# PCB2.net
KiCad netlist of a schematic drawn in EAGLE
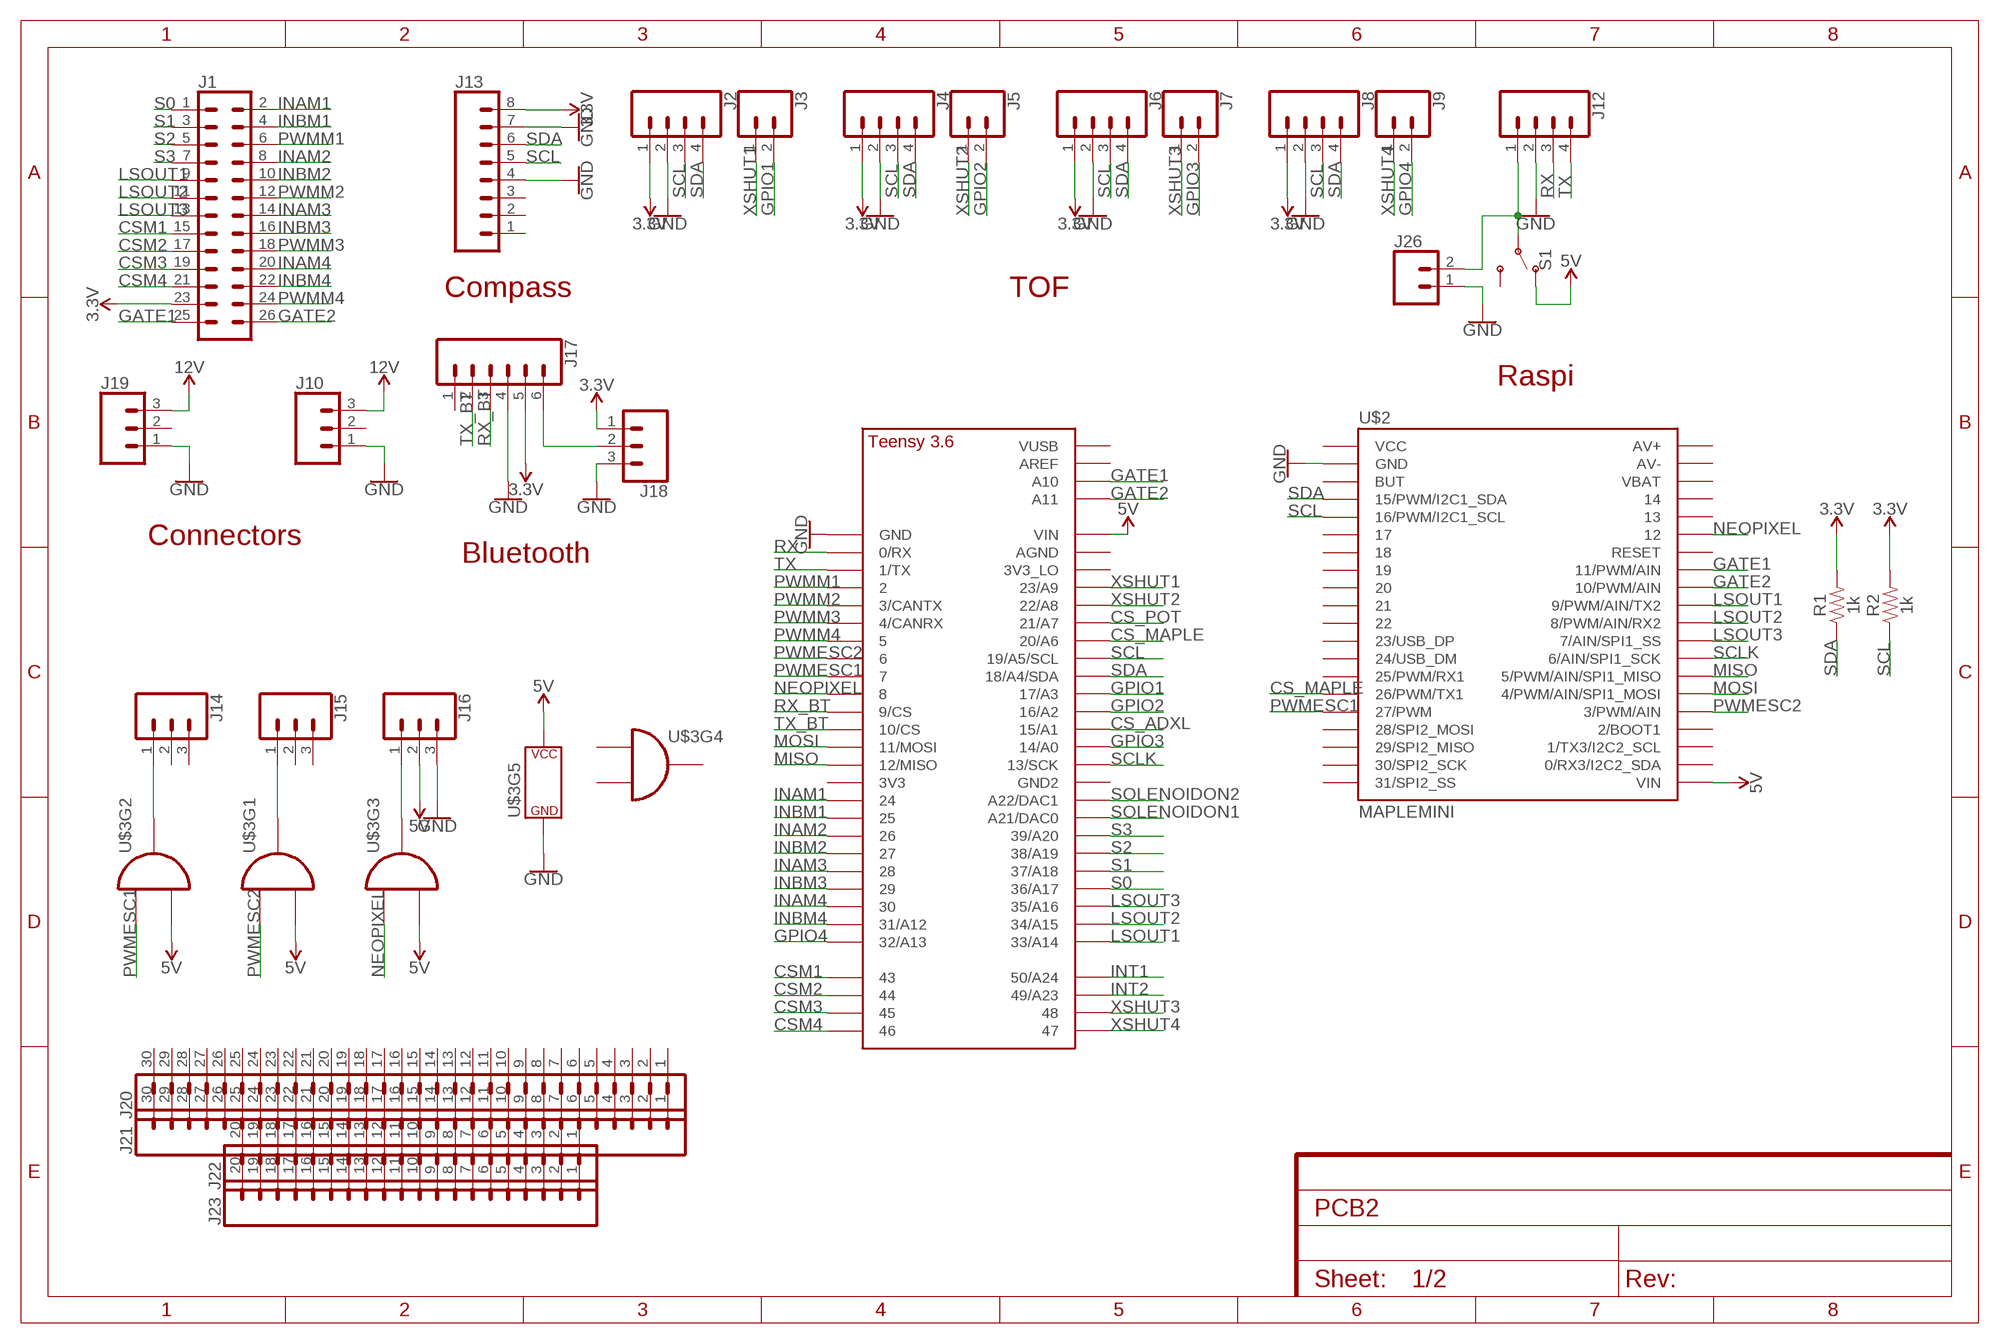
[diagram p0: schematic, sheet 1]
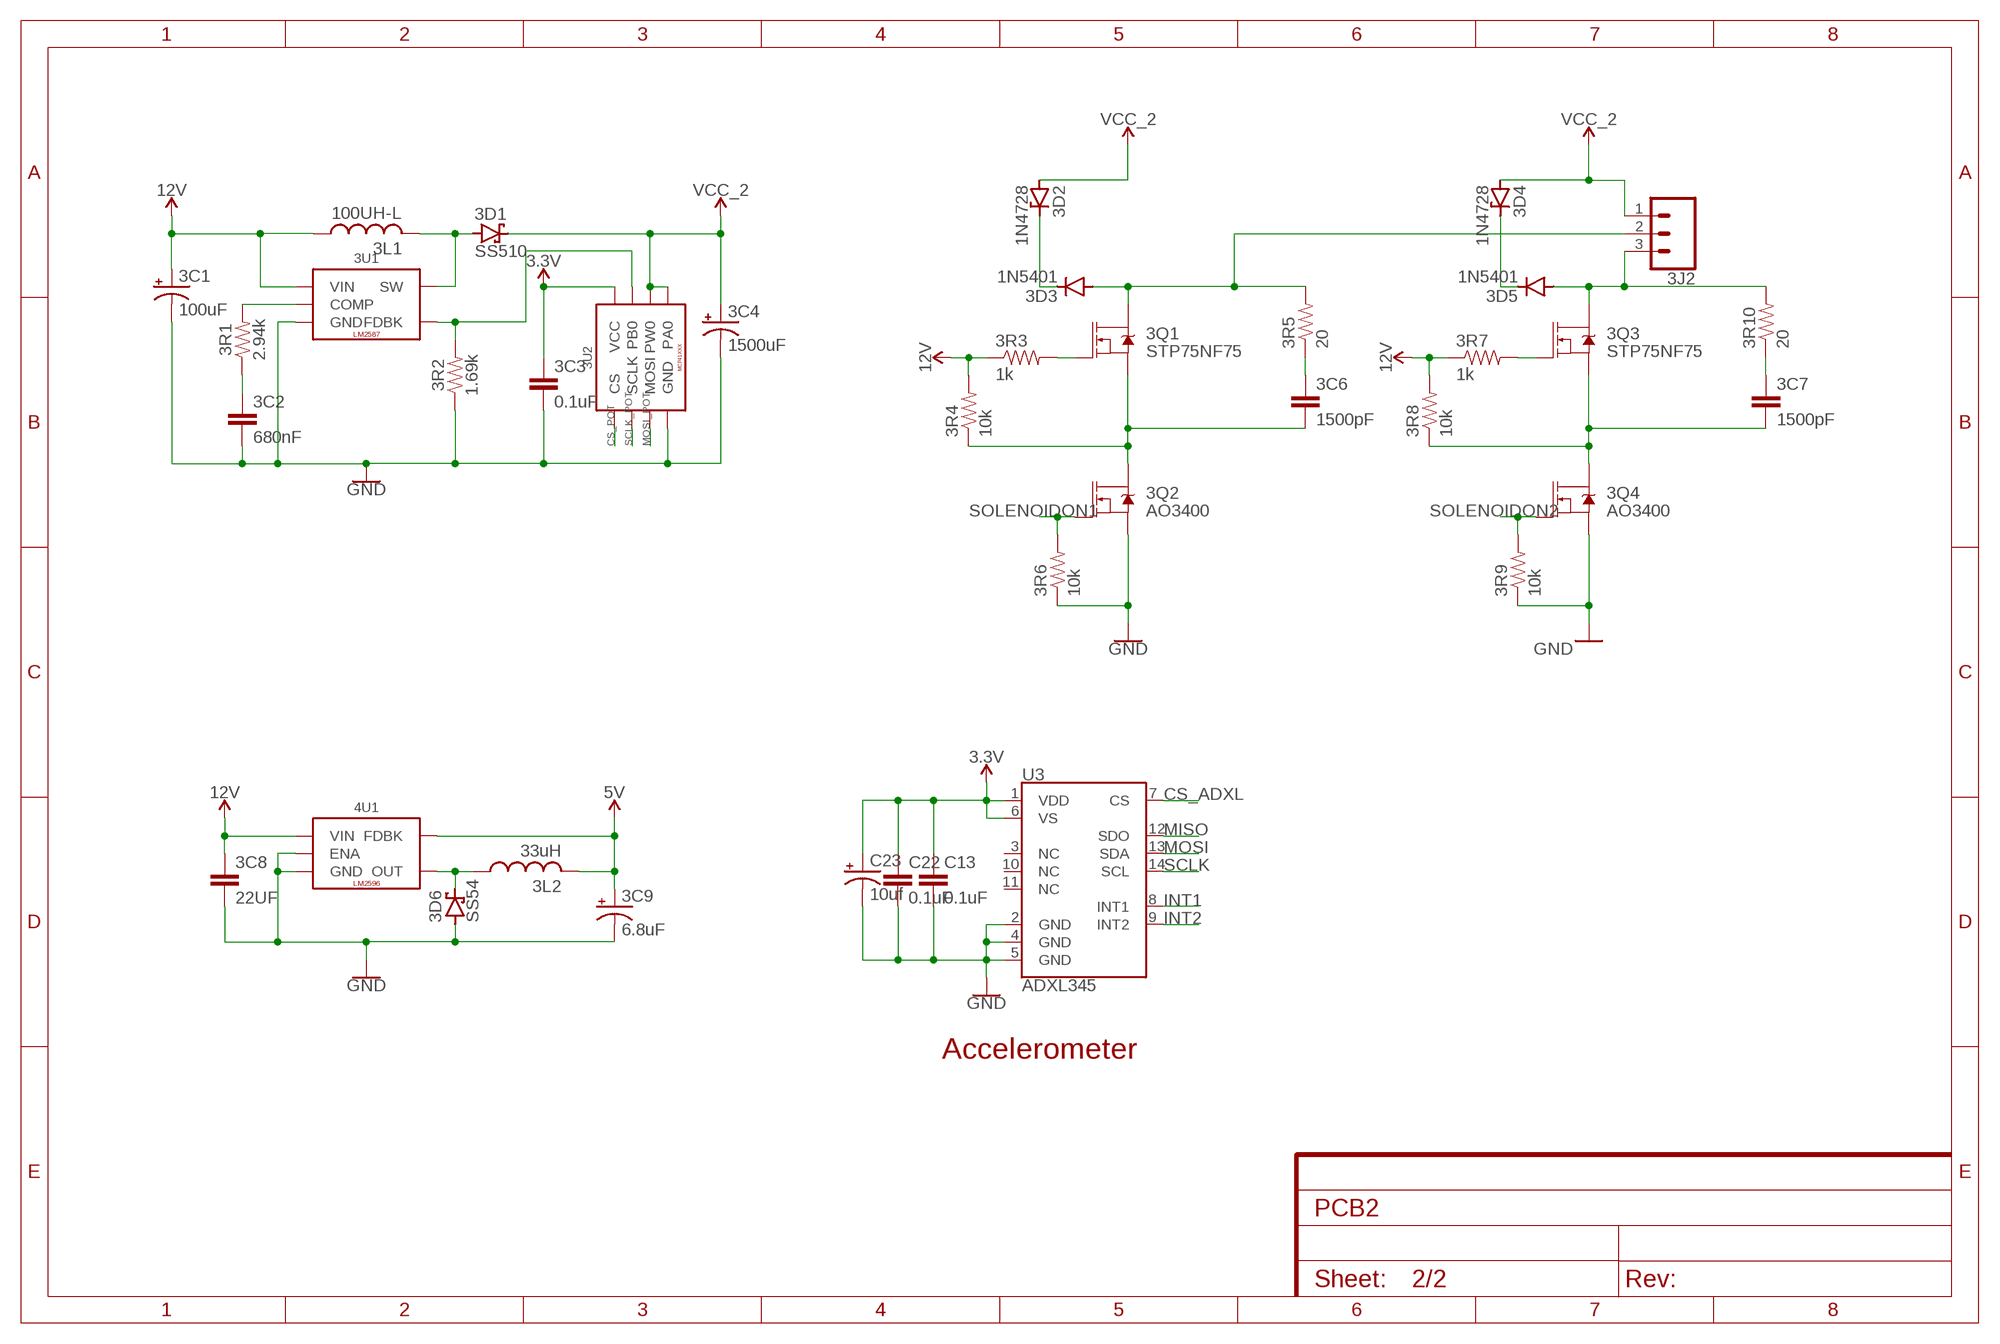
[diagram p1: schematic, sheet 2]

(export (version "E")
  (design (tool "Eeschema 10.0.6"))
  (components
    (comp (ref "J1")
      (value "CONN_13X22X13")
      (footprint "eagle-import:2X13")
      (libsource (lib "eagle-import") (part "CONN_13X22X13"))
    )
    (comp (ref "J2")
      (value "CONN_04LOCK")
      (footprint "eagle-import:1X04_LOCK")
      (libsource (lib "eagle-import") (part "CONN_04LOCK"))
    )
    (comp (ref "J3")
      (value "CONN_02LOCK")
      (footprint "eagle-import:1X02_LOCK")
      (libsource (lib "eagle-import") (part "CONN_02LOCK"))
    )
    (comp (ref "J4")
      (value "CONN_04LOCK")
      (footprint "eagle-import:1X04_LOCK")
      (libsource (lib "eagle-import") (part "CONN_04LOCK"))
    )
    (comp (ref "J5")
      (value "CONN_02LOCK")
      (footprint "eagle-import:1X02_LOCK")
      (libsource (lib "eagle-import") (part "CONN_02LOCK"))
    )
    (comp (ref "J6")
      (value "CONN_04LOCK")
      (footprint "eagle-import:1X04_LOCK")
      (libsource (lib "eagle-import") (part "CONN_04LOCK"))
    )
    (comp (ref "J7")
      (value "CONN_02LOCK")
      (footprint "eagle-import:1X02_LOCK")
      (libsource (lib "eagle-import") (part "CONN_02LOCK"))
    )
    (comp (ref "J8")
      (value "CONN_04LOCK")
      (footprint "eagle-import:1X04_LOCK")
      (libsource (lib "eagle-import") (part "CONN_04LOCK"))
    )
    (comp (ref "J9")
      (value "CONN_02LOCK")
      (footprint "eagle-import:1X02_LOCK")
      (libsource (lib "eagle-import") (part "CONN_02LOCK"))
    )
    (comp (ref "J10")
      (value "CONN_03-SCREW-5MM")
      (footprint "eagle-import:SCREWTERMINAL-5MM-3")
      (libsource (lib "eagle-import") (part "SparkFun-Connectors_513_CONN_03-SCREW-5MM"))
    )
    (comp (ref "J12")
      (value "CONN_04LOCK")
      (footprint "eagle-import:1X04_LOCK")
      (libsource (lib "eagle-import") (part "CONN_04LOCK"))
    )
    (comp (ref "J13")
      (value "CONN_08LOCK")
      (footprint "eagle-import:1X08_LOCK")
      (libsource (lib "eagle-import") (part "CONN_08LOCK"))
    )
    (comp (ref "J14")
      (value "CONN_03LOCK")
      (footprint "eagle-import:1X03_LOCK")
      (libsource (lib "eagle-import") (part "CONN_03LOCK"))
    )
    (comp (ref "J15")
      (value "CONN_03LOCK")
      (footprint "eagle-import:1X03_LOCK")
      (libsource (lib "eagle-import") (part "CONN_03LOCK"))
    )
    (comp (ref "J16")
      (value "CONN_03LOCK")
      (footprint "eagle-import:1X03_LOCK")
      (libsource (lib "eagle-import") (part "CONN_03LOCK"))
    )
    (comp (ref "J17")
      (value "CONN_06LOCK")
      (footprint "eagle-import:1X06_LOCK")
      (libsource (lib "eagle-import") (part "CONN_06LOCK"))
    )
    (comp (ref "J18")
      (value "CONN_03LOCK")
      (footprint "eagle-import:1X03_LOCK")
      (libsource (lib "eagle-import") (part "CONN_03LOCK"))
    )
    (comp (ref "J19")
      (value "CONN_03-SCREW-5MM")
      (footprint "eagle-import:SCREWTERMINAL-5MM-3")
      (libsource (lib "eagle-import") (part "SparkFun-Connectors_513_CONN_03-SCREW-5MM"))
    )
    (comp (ref "J20")
      (value "CONN_30")
      (footprint "eagle-import:1X30")
      (libsource (lib "eagle-import") (part "CONN_30"))
    )
    (comp (ref "J21")
      (value "CONN_30")
      (footprint "eagle-import:1X30")
      (libsource (lib "eagle-import") (part "CONN_30"))
    )
    (comp (ref "J22")
      (value "CONN_20")
      (footprint "eagle-import:1X20")
      (libsource (lib "eagle-import") (part "CONN_20"))
    )
    (comp (ref "J23")
      (value "CONN_20")
      (footprint "eagle-import:1X20")
      (libsource (lib "eagle-import") (part "CONN_20"))
    )
    (comp (ref "J26")
      (value "CONN_02LOCK")
      (footprint "eagle-import:1X02_LOCK")
      (libsource (lib "eagle-import") (part "SparkFun-Connectors_513_CONN_02LOCK"))
    )
    (comp (ref "R1")
      (value "1k")
      (footprint "eagle-import:0603")
      (libsource (lib "eagle-import") (part "1KOHM-0603-1/10W-1%"))
    )
    (comp (ref "R2")
      (value "1k")
      (footprint "eagle-import:0603")
      (libsource (lib "eagle-import") (part "1KOHM-0603-1/10W-1%"))
    )
    (comp (ref "S1")
      (value "SWITCH-SPDT-PTH-11.6X4.0MM-LOCK")
      (footprint "eagle-import:SWITCH_SPDT_PTH_11.6X4.0MM_LOCK")
      (libsource (lib "eagle-import") (part "SWITCH-SPDT-PTH-11.6X4.0MM-LOCK"))
    )
    (comp (ref "U$1")
      (value "TEENSY_3.5/3.6_BASIC")
      (footprint "eagle-import:TEENSY_3.5_3.6_BASIC")
      (libsource (lib "eagle-import") (part "TEENSY_3.5/3.6_BASIC"))
    )
    (comp (ref "U$2")
      (value "MAPLEMINI")
      (footprint "eagle-import:20-DIP")
      (libsource (lib "eagle-import") (part "MAPLEMINI"))
    )
    (comp (ref "U$3")
      (value "74HCT08")
      (footprint "eagle-import:SOIC-14")
      (libsource (lib "eagle-import") (part "74HCT08"))
    )
    (comp (ref "3C1")
      (value "100uF")
      (footprint "eagle-import:PANASONIC_D")
      (libsource (lib "eagle-import") (part "100UF-POLAR-25V-20%(ELEC)"))
    )
    (comp (ref "3C2")
      (value "680nF")
      (footprint "eagle-import:0603")
      (libsource (lib "eagle-import") (part "680PF-0603-50V-10%"))
    )
    (comp (ref "3C3")
      (value "0.1uF")
      (footprint "eagle-import:0603")
      (libsource (lib "eagle-import") (part "0.1UF-0603-25V-5%"))
    )
    (comp (ref "3C4")
      (value "1500uF")
      (footprint "eagle-import:1000UF-CAP")
      (libsource (lib "eagle-import") (part "1000UF-CAP"))
    )
    (comp (ref "3C6")
      (value "1500pF")
      (footprint "eagle-import:0603")
      (libsource (lib "eagle-import") (part "1.5PF-0603-50V-16.667%"))
    )
    (comp (ref "3C7")
      (value "1500pF")
      (footprint "eagle-import:0603")
      (libsource (lib "eagle-import") (part "1.5PF-0603-50V-16.667%"))
    )
    (comp (ref "3C8")
      (value "22UF")
      (footprint "eagle-import:1210")
      (libsource (lib "eagle-import") (part "22UF-1210-16V-20%"))
    )
    (comp (ref "3C9")
      (value "6.8uF")
      (footprint "eagle-import:A_3216-18R")
      (libsource (lib "eagle-import") (part "CPOL-USA/3216-18R"))
    )
    (comp (ref "3D1")
      (value "SS510")
      (footprint "eagle-import:SMB")
      (libsource (lib "eagle-import") (part "SCHOTTKY-DIODESMD"))
    )
    (comp (ref "3D2")
      (value "1N4728")
      (footprint "eagle-import:DO41Z10")
      (libsource (lib "eagle-import") (part "1N4728"))
    )
    (comp (ref "3D3")
      (value "1N5401")
      (footprint "eagle-import:DO201-15")
      (libsource (lib "eagle-import") (part "1N5400"))
    )
    (comp (ref "3D4")
      (value "1N4728")
      (footprint "eagle-import:DO41Z10")
      (libsource (lib "eagle-import") (part "1N4728"))
    )
    (comp (ref "3D5")
      (value "1N5401")
      (footprint "eagle-import:DO201-15")
      (libsource (lib "eagle-import") (part "1N5400"))
    )
    (comp (ref "3D6")
      (value "SS54")
      (footprint "eagle-import:SMB")
      (libsource (lib "eagle-import") (part "SCHOTTKY-DIODESMD"))
    )
    (comp (ref "3J2")
      (value "CONN_03-SCREW-5MM")
      (footprint "eagle-import:SCREWTERMINAL-5MM-3")
      (libsource (lib "eagle-import") (part "CONN_03-SCREW-5MM"))
    )
    (comp (ref "3L1")
      (value "100UH-L")
      (footprint "eagle-import:100UH-L")
      (libsource (lib "eagle-import") (part "100UH-L"))
    )
    (comp (ref "3L2")
      (value "33uH")
      (footprint "eagle-import:127")
      (libsource (lib "eagle-import") (part "CDRH127"))
    )
    (comp (ref "3Q1")
      (value "STP75NF75")
      (footprint "eagle-import:TO220V")
      (libsource (lib "eagle-import") (part "MOSFET-NCH-FQP30N06L"))
    )
    (comp (ref "3Q2")
      (value "AO3400")
      (footprint "eagle-import:SOT23-3")
      (libsource (lib "eagle-import") (part "MOSFET-NCH-AO3404A"))
    )
    (comp (ref "3Q3")
      (value "STP75NF75")
      (footprint "eagle-import:TO220V")
      (libsource (lib "eagle-import") (part "MOSFET-NCH-FQP30N06L"))
    )
    (comp (ref "3Q4")
      (value "AO3400")
      (footprint "eagle-import:SOT23-3")
      (libsource (lib "eagle-import") (part "MOSFET-NCH-AO3404A"))
    )
    (comp (ref "3R1")
      (value "2.94k")
      (footprint "eagle-import:0603")
      (libsource (lib "eagle-import") (part "RESISTOR0603"))
    )
    (comp (ref "3R2")
      (value "1.69k")
      (footprint "eagle-import:0603")
      (libsource (lib "eagle-import") (part "2.0KOHM-0603-1/10W-5%"))
    )
    (comp (ref "3R3")
      (value "1k")
      (footprint "eagle-import:0603")
      (libsource (lib "eagle-import") (part "1KOHM-0603-1/10W-1%"))
    )
    (comp (ref "3R4")
      (value "10k")
      (footprint "eagle-import:0603")
      (libsource (lib "eagle-import") (part "10KOHM-0603-1/10W-1%"))
    )
    (comp (ref "3R5")
      (value "20")
      (footprint "eagle-import:0603")
      (libsource (lib "eagle-import") (part "20OHM-0603-1/10W-1%"))
    )
    (comp (ref "3R6")
      (value "10k")
      (footprint "eagle-import:0603")
      (libsource (lib "eagle-import") (part "10KOHM-0603-1/10W-1%"))
    )
    (comp (ref "3R7")
      (value "1k")
      (footprint "eagle-import:0603")
      (libsource (lib "eagle-import") (part "1KOHM-0603-1/10W-1%"))
    )
    (comp (ref "3R8")
      (value "10k")
      (footprint "eagle-import:0603")
      (libsource (lib "eagle-import") (part "10KOHM-0603-1/10W-1%"))
    )
    (comp (ref "3R9")
      (value "10k")
      (footprint "eagle-import:0603")
      (libsource (lib "eagle-import") (part "10KOHM-0603-1/10W-1%"))
    )
    (comp (ref "3R10")
      (value "20")
      (footprint "eagle-import:0603")
      (libsource (lib "eagle-import") (part "20OHM-0603-1/10W-1%"))
    )
    (comp (ref "3U1")
      (value "LM2587")
      (footprint "eagle-import:TO-263")
      (libsource (lib "eagle-import") (part "LM2587"))
    )
    (comp (ref "3U2")
      (value "MCP41XXX")
      (footprint "eagle-import:SOIC-8")
      (libsource (lib "eagle-import") (part "MCP41XXX"))
    )
    (comp (ref "4U1")
      (value "LM2596")
      (footprint "eagle-import:TO-263")
      (libsource (lib "eagle-import") (part "LM2596"))
    )
    (comp (ref "C13")
      (value "0.1uF")
      (footprint "eagle-import:0603")
      (libsource (lib "eagle-import") (part "0.1UF-0603-100V-10%"))
    )
    (comp (ref "C22")
      (value "0.1uF")
      (footprint "eagle-import:0603")
      (libsource (lib "eagle-import") (part "0.1UF-0603-100V-10%"))
    )
    (comp (ref "C23")
      (value "10uf")
      (footprint "eagle-import:R_2012-12R")
      (libsource (lib "eagle-import") (part "CPOL-USR/2012-12R"))
    )
    (comp (ref "U3")
      (value "ADXL345")
      (footprint "eagle-import:LGA-14")
      (libsource (lib "eagle-import") (part "ADXL345"))
    )
  )
  (nets
    (net (code "1") (name "3.3V") (class "Default")
      (node (ref "3C3") (pin "1") (pinfunction "1_1") (pintype "passive"))
      (node (ref "3U2") (pin "8") (pinfunction "VCC_8") (pintype "power_in"))
      (node (ref "C13") (pin "1") (pinfunction "1_1") (pintype "passive"))
      (node (ref "C22") (pin "1") (pinfunction "1_1") (pintype "passive"))
      (node (ref "C23") (pin "+") (pinfunction "+_+") (pintype "passive"))
      (node (ref "J1") (pin "23") (pinfunction "23_23") (pintype "passive"))
      (node (ref "J13") (pin "8") (pinfunction "8_8") (pintype "passive"))
      (node (ref "J17") (pin "5") (pinfunction "5_5") (pintype "passive"))
      (node (ref "J18") (pin "1") (pinfunction "1_1") (pintype "passive"))
      (node (ref "J2") (pin "1") (pinfunction "1_1") (pintype "passive"))
      (node (ref "J4") (pin "1") (pinfunction "1_1") (pintype "passive"))
      (node (ref "J6") (pin "1") (pinfunction "1_1") (pintype "passive"))
      (node (ref "J8") (pin "1") (pinfunction "1_1") (pintype "passive"))
      (node (ref "R1") (pin "2") (pinfunction "2_2") (pintype "passive"))
      (node (ref "R2") (pin "2") (pinfunction "2_2") (pintype "passive"))
      (node (ref "U3") (pin "1") (pinfunction "VDD_1") (pintype "bidirectional"))
      (node (ref "U3") (pin "6") (pinfunction "VS_6") (pintype "bidirectional"))
    )
    (net (code "2") (name "5V") (class "Default")
      (node (ref "3C9") (pin "+") (pinfunction "+_+") (pintype "passive"))
      (node (ref "3L2") (pin "2") (pinfunction "2_2") (pintype "passive"))
      (node (ref "4U1") (pin "P4") (pinfunction "FDBK_P4") (pintype "output"))
      (node (ref "J16") (pin "2") (pinfunction "2_2") (pintype "passive"))
      (node (ref "S1") (pin "1") (pinfunction "O_1") (pintype "passive"))
      (node (ref "U$1") (pin "VIN") (pinfunction "VIN_VIN") (pintype "bidirectional"))
      (node (ref "U$2") (pin "21") (pinfunction "VIN_21") (pintype "bidirectional"))
      (node (ref "U$3") (pin "P10") (pinfunction "I1_P10") (pintype "input"))
      (node (ref "U$3") (pin "P14") (pinfunction "P$V+_P14") (pintype "bidirectional"))
      (node (ref "U$3") (pin "P2") (pinfunction "I1_P2") (pintype "input"))
      (node (ref "U$3") (pin "P5") (pinfunction "I1_P5") (pintype "input"))
    )
    (net (code "3") (name "12V") (class "Default")
      (node (ref "3C1") (pin "+") (pinfunction "+_+") (pintype "passive"))
      (node (ref "3C8") (pin "1") (pinfunction "1_1") (pintype "passive"))
      (node (ref "3L1") (pin "P1") (pinfunction "1_P1") (pintype "passive"))
      (node (ref "3R3") (pin "1") (pinfunction "1_1") (pintype "passive"))
      (node (ref "3R4") (pin "2") (pinfunction "2_2") (pintype "passive"))
      (node (ref "3R7") (pin "1") (pinfunction "1_1") (pintype "passive"))
      (node (ref "3R8") (pin "2") (pinfunction "2_2") (pintype "passive"))
      (node (ref "3U1") (pin "P5") (pinfunction "VIN_P5") (pintype "power_in"))
      (node (ref "4U1") (pin "P1") (pinfunction "VIN_P1") (pintype "power_in"))
      (node (ref "J10") (pin "3") (pinfunction "3_3") (pintype "passive"))
      (node (ref "J19") (pin "3") (pinfunction "3_3") (pintype "passive"))
    )
    (net (code "4") (name "CSM1") (class "Default")
      (node (ref "J1") (pin "15") (pinfunction "15_15") (pintype "passive"))
      (node (ref "U$1") (pin "43") (pinfunction "43_43") (pintype "bidirectional"))
    )
    (net (code "5") (name "CSM2") (class "Default")
      (node (ref "J1") (pin "17") (pinfunction "17_17") (pintype "passive"))
      (node (ref "U$1") (pin "44") (pinfunction "44_44") (pintype "bidirectional"))
    )
    (net (code "6") (name "CSM3") (class "Default")
      (node (ref "J1") (pin "19") (pinfunction "19_19") (pintype "passive"))
      (node (ref "U$1") (pin "45") (pinfunction "45_45") (pintype "bidirectional"))
    )
    (net (code "7") (name "CSM4") (class "Default")
      (node (ref "J1") (pin "21") (pinfunction "21_21") (pintype "passive"))
      (node (ref "U$1") (pin "46") (pinfunction "46_46") (pintype "bidirectional"))
    )
    (net (code "8") (name "CS_ADXL") (class "Default")
      (node (ref "U$1") (pin "15/A1") (pinfunction "15/A1_15/A1") (pintype "bidirectional"))
      (node (ref "U3") (pin "7") (pinfunction "CS_7") (pintype "bidirectional"))
    )
    (net (code "9") (name "CS_MAPLE") (class "Default")
      (node (ref "U$1") (pin "20/A6") (pinfunction "20/A6_20/A6") (pintype "bidirectional"))
      (node (ref "U$2") (pin "15") (pinfunction "26/PWM/TX1_15") (pintype "bidirectional"))
    )
    (net (code "10") (name "CS_POT") (class "Default")
      (node (ref "3U2") (pin "1") (pinfunction "CS_1") (pintype "input"))
      (node (ref "U$1") (pin "21/A7") (pinfunction "21/A7_21/A7") (pintype "bidirectional"))
    )
    (net (code "11") (name "GATE1") (class "Default")
      (node (ref "J1") (pin "25") (pinfunction "25_25") (pintype "passive"))
      (node (ref "U$1") (pin "A10") (pinfunction "A10_A10") (pintype "bidirectional"))
      (node (ref "U$2") (pin "33") (pinfunction "11/PWM/AIN_33") (pintype "bidirectional"))
    )
    (net (code "12") (name "GATE2") (class "Default")
      (node (ref "J1") (pin "26") (pinfunction "26_26") (pintype "passive"))
      (node (ref "U$1") (pin "A11") (pinfunction "A11_A11") (pintype "bidirectional"))
      (node (ref "U$2") (pin "32") (pinfunction "10/PWM/AIN_32") (pintype "bidirectional"))
    )
    (net (code "13") (name "GND") (class "Default")
      (node (ref "3C1") (pin "-") (pinfunction "-_-") (pintype "passive"))
      (node (ref "3C2") (pin "2") (pinfunction "2_2") (pintype "passive"))
      (node (ref "3C3") (pin "2") (pinfunction "2_2") (pintype "passive"))
      (node (ref "3C4") (pin "-") (pinfunction "-_-") (pintype "passive"))
      (node (ref "3C8") (pin "2") (pinfunction "2_2") (pintype "passive"))
      (node (ref "3C9") (pin "-") (pinfunction "-_-") (pintype "passive"))
      (node (ref "3D6") (pin "A") (pinfunction "A_A") (pintype "passive"))
      (node (ref "3Q2") (pin "2") (pinfunction "S_2") (pintype "bidirectional"))
      (node (ref "3Q4") (pin "2") (pinfunction "S_2") (pintype "bidirectional"))
      (node (ref "3R2") (pin "1") (pinfunction "1_1") (pintype "passive"))
      (node (ref "3R6") (pin "1") (pinfunction "1_1") (pintype "passive"))
      (node (ref "3R9") (pin "1") (pinfunction "1_1") (pintype "passive"))
      (node (ref "3U1") (pin "P3") (pinfunction "GND_P3") (pintype "power_in"))
      (node (ref "3U2") (pin "4") (pinfunction "GND_4") (pintype "power_in"))
      (node (ref "4U1") (pin "P3") (pinfunction "GND_P3") (pintype "power_in"))
      (node (ref "4U1") (pin "P5") (pinfunction "ENA_P5") (pintype "bidirectional"))
      (node (ref "4U1") (pin "TAB") (pinfunction "GND_TAB") (pintype "power_in"))
      (node (ref "C13") (pin "2") (pinfunction "2_2") (pintype "passive"))
      (node (ref "C22") (pin "2") (pinfunction "2_2") (pintype "passive"))
      (node (ref "C23") (pin "-") (pinfunction "-_-") (pintype "passive"))
      (node (ref "J10") (pin "1") (pinfunction "1_1") (pintype "passive"))
      (node (ref "J12") (pin "2") (pinfunction "2_2") (pintype "passive"))
      (node (ref "J13") (pin "4") (pinfunction "4_4") (pintype "passive"))
      (node (ref "J13") (pin "7") (pinfunction "7_7") (pintype "passive"))
      (node (ref "J16") (pin "3") (pinfunction "3_3") (pintype "passive"))
      (node (ref "J17") (pin "4") (pinfunction "4_4") (pintype "passive"))
      (node (ref "J18") (pin "3") (pinfunction "3_3") (pintype "passive"))
      (node (ref "J19") (pin "1") (pinfunction "1_1") (pintype "passive"))
      (node (ref "J2") (pin "2") (pinfunction "2_2") (pintype "passive"))
      (node (ref "J26") (pin "1") (pinfunction "1_1") (pintype "passive"))
      (node (ref "J4") (pin "2") (pinfunction "2_2") (pintype "passive"))
      (node (ref "J6") (pin "2") (pinfunction "2_2") (pintype "passive"))
      (node (ref "J8") (pin "2") (pinfunction "2_2") (pintype "passive"))
      (node (ref "U$1") (pin "GND") (pinfunction "GND_GND") (pintype "bidirectional"))
      (node (ref "U$2") (pin "2") (pinfunction "GND_2") (pintype "bidirectional"))
      (node (ref "U$3") (pin "P7") (pinfunction "P$V-_P7") (pintype "bidirectional"))
      (node (ref "U3") (pin "2") (pinfunction "GND_2") (pintype "bidirectional"))
      (node (ref "U3") (pin "4") (pinfunction "GND_4") (pintype "bidirectional"))
      (node (ref "U3") (pin "5") (pinfunction "GND_5") (pintype "bidirectional"))
    )
    (net (code "14") (name "GPIO1") (class "Default")
      (node (ref "J3") (pin "2") (pinfunction "2_2") (pintype "passive"))
      (node (ref "U$1") (pin "17/A3") (pinfunction "17/A3_17/A3") (pintype "bidirectional"))
    )
    (net (code "15") (name "GPIO2") (class "Default")
      (node (ref "J5") (pin "2") (pinfunction "2_2") (pintype "passive"))
      (node (ref "U$1") (pin "16/A2") (pinfunction "16/A2_16/A2") (pintype "bidirectional"))
    )
    (net (code "16") (name "GPIO3") (class "Default")
      (node (ref "J7") (pin "2") (pinfunction "2_2") (pintype "passive"))
      (node (ref "U$1") (pin "14/A0") (pinfunction "14/A0_14/A0") (pintype "bidirectional"))
    )
    (net (code "17") (name "GPIO4") (class "Default")
      (node (ref "J9") (pin "2") (pinfunction "2_2") (pintype "passive"))
      (node (ref "U$1") (pin "32/A13") (pinfunction "32/A13_32/A13") (pintype "bidirectional"))
    )
    (net (code "18") (name "INAM1") (class "Default")
      (node (ref "J1") (pin "2") (pinfunction "2_2") (pintype "passive"))
      (node (ref "U$1") (pin "24") (pinfunction "24_24") (pintype "bidirectional"))
    )
    (net (code "19") (name "INAM2") (class "Default")
      (node (ref "J1") (pin "8") (pinfunction "8_8") (pintype "passive"))
      (node (ref "U$1") (pin "26") (pinfunction "26_26") (pintype "bidirectional"))
    )
    (net (code "20") (name "INAM3") (class "Default")
      (node (ref "J1") (pin "14") (pinfunction "14_14") (pintype "passive"))
      (node (ref "U$1") (pin "28") (pinfunction "28_28") (pintype "bidirectional"))
    )
    (net (code "21") (name "INAM4") (class "Default")
      (node (ref "J1") (pin "20") (pinfunction "20_20") (pintype "passive"))
      (node (ref "U$1") (pin "30") (pinfunction "30_30") (pintype "bidirectional"))
    )
    (net (code "22") (name "INBM1") (class "Default")
      (node (ref "J1") (pin "4") (pinfunction "4_4") (pintype "passive"))
      (node (ref "U$1") (pin "25") (pinfunction "25_25") (pintype "bidirectional"))
    )
    (net (code "23") (name "INBM2") (class "Default")
      (node (ref "J1") (pin "10") (pinfunction "10_10") (pintype "passive"))
      (node (ref "U$1") (pin "27") (pinfunction "27_27") (pintype "bidirectional"))
    )
    (net (code "24") (name "INBM3") (class "Default")
      (node (ref "J1") (pin "16") (pinfunction "16_16") (pintype "passive"))
      (node (ref "U$1") (pin "29") (pinfunction "29_29") (pintype "bidirectional"))
    )
    (net (code "25") (name "INBM4") (class "Default")
      (node (ref "J1") (pin "22") (pinfunction "22_22") (pintype "passive"))
      (node (ref "U$1") (pin "31/A12") (pinfunction "31/A12_31/A12") (pintype "bidirectional"))
    )
    (net (code "26") (name "INT1") (class "Default")
      (node (ref "U$1") (pin "50/A24") (pinfunction "50/A24_50/A24") (pintype "bidirectional"))
      (node (ref "U3") (pin "8") (pinfunction "INT1_8") (pintype "bidirectional"))
    )
    (net (code "27") (name "INT2") (class "Default")
      (node (ref "U$1") (pin "49/A23") (pinfunction "49/A23_49/A23") (pintype "bidirectional"))
      (node (ref "U3") (pin "9") (pinfunction "INT2_9") (pintype "bidirectional"))
    )
    (net (code "28") (name "LSOUT1") (class "Default")
      (node (ref "J1") (pin "9") (pinfunction "9_9") (pintype "passive"))
      (node (ref "U$1") (pin "33/A14") (pinfunction "33/A14_33/A14") (pintype "bidirectional"))
      (node (ref "U$2") (pin "31") (pinfunction "9/PWM/AIN/TX2_31") (pintype "bidirectional"))
    )
    (net (code "29") (name "LSOUT2") (class "Default")
      (node (ref "J1") (pin "11") (pinfunction "11_11") (pintype "passive"))
      (node (ref "U$1") (pin "34/A15") (pinfunction "34/A15_34/A15") (pintype "bidirectional"))
      (node (ref "U$2") (pin "30") (pinfunction "8/PWM/AIN/RX2_30") (pintype "bidirectional"))
    )
    (net (code "30") (name "LSOUT3") (class "Default")
      (node (ref "J1") (pin "13") (pinfunction "13_13") (pintype "passive"))
      (node (ref "U$1") (pin "35/A16") (pinfunction "35/A16_35/A16") (pintype "bidirectional"))
      (node (ref "U$2") (pin "29") (pinfunction "7/AIN/SPI1_SS_29") (pintype "bidirectional"))
    )
    (net (code "31") (name "MISO") (class "Default")
      (node (ref "U$1") (pin "12/MISO") (pinfunction "12/MISO_12/MISO") (pintype "bidirectional"))
      (node (ref "U$2") (pin "27") (pinfunction "5/PWM/AIN/SPI1_MISO_27") (pintype "bidirectional"))
      (node (ref "U3") (pin "12") (pinfunction "SDO_12") (pintype "bidirectional"))
    )
    (net (code "32") (name "MOSI") (class "Default")
      (node (ref "U$1") (pin "11/MOSI") (pinfunction "11/MOSI_11/MOSI") (pintype "bidirectional"))
      (node (ref "U$2") (pin "26") (pinfunction "4/PWM/AIN/SPI1_MOSI_26") (pintype "bidirectional"))
      (node (ref "U3") (pin "13") (pinfunction "SDA_13") (pintype "bidirectional"))
    )
    (net (code "33") (name "MOSI_POT") (class "Default")
      (node (ref "3U2") (pin "3") (pinfunction "MOSI_3") (pintype "input"))
    )
    (net (code "34") (name "NEOPIXEL") (class "Default")
      (node (ref "U$1") (pin "8") (pinfunction "8_8") (pintype "bidirectional"))
      (node (ref "U$2") (pin "35") (pinfunction "12_35") (pintype "bidirectional"))
      (node (ref "U$3") (pin "P9") (pinfunction "I0_P9") (pintype "input"))
    )
    (net (code "35") (name "Net-(3C2-Pad1)") (class "Default")
      (node (ref "3C2") (pin "1") (pinfunction "1_1") (pintype "passive"))
      (node (ref "3R1") (pin "1") (pinfunction "1_1") (pintype "passive"))
    )
    (net (code "36") (name "Net-(3C6-Pad1)") (class "Default")
      (node (ref "3C6") (pin "1") (pinfunction "1_1") (pintype "passive"))
      (node (ref "3R5") (pin "1") (pinfunction "1_1") (pintype "passive"))
    )
    (net (code "37") (name "Net-(3C7-Pad1)") (class "Default")
      (node (ref "3C7") (pin "1") (pinfunction "1_1") (pintype "passive"))
      (node (ref "3R10") (pin "1") (pinfunction "1_1") (pintype "passive"))
    )
    (net (code "38") (name "Net-(3D2-PadC)") (class "Default")
      (node (ref "3D2") (pin "C") (pinfunction "C_C") (pintype "passive"))
      (node (ref "3D3") (pin "C") (pinfunction "C_C") (pintype "passive"))
    )
    (net (code "39") (name "Net-(3D4-PadC)") (class "Default")
      (node (ref "3D4") (pin "C") (pinfunction "C_C") (pintype "passive"))
      (node (ref "3D5") (pin "C") (pinfunction "C_C") (pintype "passive"))
    )
    (net (code "40") (name "Net-(3L1-2)") (class "Default")
      (node (ref "3D1") (pin "A") (pinfunction "A_A") (pintype "passive"))
      (node (ref "3L1") (pin "P2") (pinfunction "2_P2") (pintype "passive"))
      (node (ref "3U1") (pin "P4") (pinfunction "SW_P4") (pintype "output"))
    )
    (net (code "41") (name "Net-(3Q1-D)") (class "Default")
      (node (ref "3D3") (pin "A") (pinfunction "A_A") (pintype "passive"))
      (node (ref "3J2") (pin "2") (pinfunction "2_2") (pintype "passive"))
      (node (ref "3Q1") (pin "2") (pinfunction "D_2") (pintype "bidirectional"))
      (node (ref "3R5") (pin "2") (pinfunction "2_2") (pintype "passive"))
    )
    (net (code "42") (name "Net-(3Q1-G)") (class "Default")
      (node (ref "3Q1") (pin "1") (pinfunction "G_1") (pintype "bidirectional"))
      (node (ref "3R3") (pin "2") (pinfunction "2_2") (pintype "passive"))
    )
    (net (code "43") (name "Net-(3Q1-S)") (class "Default")
      (node (ref "3C6") (pin "2") (pinfunction "2_2") (pintype "passive"))
      (node (ref "3Q1") (pin "3") (pinfunction "S_3") (pintype "bidirectional"))
      (node (ref "3Q2") (pin "3") (pinfunction "D_3") (pintype "bidirectional"))
      (node (ref "3R4") (pin "1") (pinfunction "1_1") (pintype "passive"))
    )
    (net (code "44") (name "Net-(3Q3-D)") (class "Default")
      (node (ref "3D5") (pin "A") (pinfunction "A_A") (pintype "passive"))
      (node (ref "3J2") (pin "3") (pinfunction "3_3") (pintype "passive"))
      (node (ref "3Q3") (pin "2") (pinfunction "D_2") (pintype "bidirectional"))
      (node (ref "3R10") (pin "2") (pinfunction "2_2") (pintype "passive"))
    )
    (net (code "45") (name "Net-(3Q3-G)") (class "Default")
      (node (ref "3Q3") (pin "1") (pinfunction "G_1") (pintype "bidirectional"))
      (node (ref "3R7") (pin "2") (pinfunction "2_2") (pintype "passive"))
    )
    (net (code "46") (name "Net-(3Q3-S)") (class "Default")
      (node (ref "3C7") (pin "2") (pinfunction "2_2") (pintype "passive"))
      (node (ref "3Q3") (pin "3") (pinfunction "S_3") (pintype "bidirectional"))
      (node (ref "3Q4") (pin "3") (pinfunction "D_3") (pintype "bidirectional"))
      (node (ref "3R8") (pin "1") (pinfunction "1_1") (pintype "passive"))
    )
    (net (code "47") (name "Net-(3U1-COMP)") (class "Default")
      (node (ref "3R1") (pin "2") (pinfunction "2_2") (pintype "passive"))
      (node (ref "3U1") (pin "P1") (pinfunction "COMP_P1") (pintype "bidirectional"))
    )
    (net (code "48") (name "Net-(3U1-FDBK)") (class "Default")
      (node (ref "3R2") (pin "2") (pinfunction "2_2") (pintype "passive"))
      (node (ref "3U1") (pin "P2") (pinfunction "FDBK_P2") (pintype "input"))
      (node (ref "3U2") (pin "7") (pinfunction "PB0_7") (pintype "bidirectional"))
    )
    (net (code "49") (name "Net-(4U1-OUT)") (class "Default")
      (node (ref "3D6") (pin "C") (pinfunction "C_C") (pintype "passive"))
      (node (ref "3L2") (pin "1") (pinfunction "1_1") (pintype "passive"))
      (node (ref "4U1") (pin "P2") (pinfunction "OUT_P2") (pintype "input"))
    )
    (net (code "50") (name "Net-(J17-Pad6)") (class "Default")
      (node (ref "J17") (pin "6") (pinfunction "6_6") (pintype "passive"))
      (node (ref "J18") (pin "2") (pinfunction "2_2") (pintype "passive"))
    )
    (net (code "51") (name "Net-(S1-P)") (class "Default")
      (node (ref "J12") (pin "1") (pinfunction "1_1") (pintype "passive"))
      (node (ref "J26") (pin "2") (pinfunction "2_2") (pintype "passive"))
      (node (ref "S1") (pin "2") (pinfunction "P_2") (pintype "passive"))
    )
    (net (code "52") (name "Net-(U$3A-O)") (class "Default")
      (node (ref "J15") (pin "1") (pinfunction "1_1") (pintype "passive"))
      (node (ref "U$3") (pin "P3") (pinfunction "O_P3") (pintype "output"))
    )
    (net (code "53") (name "Net-(U$3B-O)") (class "Default")
      (node (ref "J14") (pin "1") (pinfunction "1_1") (pintype "passive"))
      (node (ref "U$3") (pin "P6") (pinfunction "O_P6") (pintype "output"))
    )
    (net (code "54") (name "Net-(U$3C-O)") (class "Default")
      (node (ref "J16") (pin "1") (pinfunction "1_1") (pintype "passive"))
      (node (ref "U$3") (pin "P8") (pinfunction "O_P8") (pintype "output"))
    )
    (net (code "55") (name "PWMESC1") (class "Default")
      (node (ref "U$1") (pin "7") (pinfunction "7_7") (pintype "bidirectional"))
      (node (ref "U$2") (pin "16") (pinfunction "27/PWM_16") (pintype "bidirectional"))
      (node (ref "U$3") (pin "P4") (pinfunction "I0_P4") (pintype "input"))
    )
    (net (code "56") (name "PWMESC2") (class "Default")
      (node (ref "U$1") (pin "6") (pinfunction "6_6") (pintype "bidirectional"))
      (node (ref "U$2") (pin "25") (pinfunction "3/PWM/AIN_25") (pintype "bidirectional"))
      (node (ref "U$3") (pin "P1") (pinfunction "I0_P1") (pintype "input"))
    )
    (net (code "57") (name "PWMM1") (class "Default")
      (node (ref "J1") (pin "6") (pinfunction "6_6") (pintype "passive"))
      (node (ref "U$1") (pin "2") (pinfunction "2_2") (pintype "bidirectional"))
    )
    (net (code "58") (name "PWMM2") (class "Default")
      (node (ref "J1") (pin "12") (pinfunction "12_12") (pintype "passive"))
      (node (ref "U$1") (pin "3/CANTX") (pinfunction "3/CANTX_3/CANTX") (pintype "bidirectional"))
    )
    (net (code "59") (name "PWMM3") (class "Default")
      (node (ref "J1") (pin "18") (pinfunction "18_18") (pintype "passive"))
      (node (ref "U$1") (pin "4/CANRX") (pinfunction "4/CANRX_4/CANRX") (pintype "bidirectional"))
    )
    (net (code "60") (name "PWMM4") (class "Default")
      (node (ref "J1") (pin "24") (pinfunction "24_24") (pintype "passive"))
      (node (ref "U$1") (pin "5") (pinfunction "5_5") (pintype "bidirectional"))
    )
    (net (code "61") (name "RX") (class "Default")
      (node (ref "J12") (pin "3") (pinfunction "3_3") (pintype "passive"))
      (node (ref "U$1") (pin "0/RX") (pinfunction "0/RX_0/RX") (pintype "bidirectional"))
    )
    (net (code "62") (name "RX_BT") (class "Default")
      (node (ref "J17") (pin "3") (pinfunction "3_3") (pintype "passive"))
      (node (ref "U$1") (pin "9/CS") (pinfunction "9/CS_9/CS") (pintype "bidirectional"))
    )
    (net (code "63") (name "S0") (class "Default")
      (node (ref "J1") (pin "1") (pinfunction "1_1") (pintype "passive"))
      (node (ref "U$1") (pin "36/A17") (pinfunction "36/A17_36/A17") (pintype "bidirectional"))
    )
    (net (code "64") (name "S1") (class "Default")
      (node (ref "J1") (pin "3") (pinfunction "3_3") (pintype "passive"))
      (node (ref "U$1") (pin "37/A18") (pinfunction "37/A18_37/A18") (pintype "bidirectional"))
    )
    (net (code "65") (name "S2") (class "Default")
      (node (ref "J1") (pin "5") (pinfunction "5_5") (pintype "passive"))
      (node (ref "U$1") (pin "38/A19") (pinfunction "38/A19_38/A19") (pintype "bidirectional"))
    )
    (net (code "66") (name "S3") (class "Default")
      (node (ref "J1") (pin "7") (pinfunction "7_7") (pintype "passive"))
      (node (ref "U$1") (pin "39/A20") (pinfunction "39/A20_39/A20") (pintype "bidirectional"))
    )
    (net (code "67") (name "SCL") (class "Default")
      (node (ref "J13") (pin "5") (pinfunction "5_5") (pintype "passive"))
      (node (ref "J2") (pin "3") (pinfunction "3_3") (pintype "passive"))
      (node (ref "J4") (pin "3") (pinfunction "3_3") (pintype "passive"))
      (node (ref "J6") (pin "3") (pinfunction "3_3") (pintype "passive"))
      (node (ref "J8") (pin "3") (pinfunction "3_3") (pintype "passive"))
      (node (ref "R2") (pin "1") (pinfunction "1_1") (pintype "passive"))
      (node (ref "U$1") (pin "19/A5/SCL") (pinfunction "19/A5/SCL_19/A5/SCL") (pintype "bidirectional"))
      (node (ref "U$2") (pin "5") (pinfunction "16/PWM/I2C1_SCL_5") (pintype "bidirectional"))
    )
    (net (code "68") (name "SCLK") (class "Default")
      (node (ref "U$1") (pin "13/SCK") (pinfunction "13/SCK_13/SCK") (pintype "bidirectional"))
      (node (ref "U$2") (pin "28") (pinfunction "6/AIN/SPI1_SCK_28") (pintype "bidirectional"))
      (node (ref "U3") (pin "14") (pinfunction "SCL_14") (pintype "bidirectional"))
    )
    (net (code "69") (name "SCLK_POT") (class "Default")
      (node (ref "3U2") (pin "2") (pinfunction "SCLK_2") (pintype "input"))
    )
    (net (code "70") (name "SDA") (class "Default")
      (node (ref "J13") (pin "6") (pinfunction "6_6") (pintype "passive"))
      (node (ref "J2") (pin "4") (pinfunction "4_4") (pintype "passive"))
      (node (ref "J4") (pin "4") (pinfunction "4_4") (pintype "passive"))
      (node (ref "J6") (pin "4") (pinfunction "4_4") (pintype "passive"))
      (node (ref "J8") (pin "4") (pinfunction "4_4") (pintype "passive"))
      (node (ref "R1") (pin "1") (pinfunction "1_1") (pintype "passive"))
      (node (ref "U$1") (pin "18/A4/SDA") (pinfunction "18/A4/SDA_18/A4/SDA") (pintype "bidirectional"))
      (node (ref "U$2") (pin "4") (pinfunction "15/PWM/I2C1_SDA_4") (pintype "bidirectional"))
    )
    (net (code "71") (name "SOLENOIDON1") (class "Default")
      (node (ref "3Q2") (pin "1") (pinfunction "G_1") (pintype "bidirectional"))
      (node (ref "3R6") (pin "2") (pinfunction "2_2") (pintype "passive"))
      (node (ref "U$1") (pin "21/DAC0") (pinfunction "A21/DAC0_21/DAC0") (pintype "bidirectional"))
    )
    (net (code "72") (name "SOLENOIDON2") (class "Default")
      (node (ref "3Q4") (pin "1") (pinfunction "G_1") (pintype "bidirectional"))
      (node (ref "3R9") (pin "2") (pinfunction "2_2") (pintype "passive"))
      (node (ref "U$1") (pin "A22/DAC1") (pinfunction "A22/DAC1_A22/DAC1") (pintype "bidirectional"))
    )
    (net (code "73") (name "TX") (class "Default")
      (node (ref "J12") (pin "4") (pinfunction "4_4") (pintype "passive"))
      (node (ref "U$1") (pin "1/TX") (pinfunction "1/TX_1/TX") (pintype "bidirectional"))
    )
    (net (code "74") (name "TX_BT") (class "Default")
      (node (ref "J17") (pin "2") (pinfunction "2_2") (pintype "passive"))
      (node (ref "U$1") (pin "10/CS") (pinfunction "10/CS_10/CS") (pintype "bidirectional"))
    )
    (net (code "75") (name "VCC_2") (class "Default")
      (node (ref "3C4") (pin "+") (pinfunction "+_+") (pintype "passive"))
      (node (ref "3D1") (pin "C") (pinfunction "C_C") (pintype "passive"))
      (node (ref "3D2") (pin "A") (pinfunction "A_A") (pintype "passive"))
      (node (ref "3D4") (pin "A") (pinfunction "A_A") (pintype "passive"))
      (node (ref "3J2") (pin "1") (pinfunction "1_1") (pintype "passive"))
      (node (ref "3U2") (pin "5") (pinfunction "PA0_5") (pintype "bidirectional"))
      (node (ref "3U2") (pin "6") (pinfunction "PW0_6") (pintype "bidirectional"))
    )
    (net (code "76") (name "XSHUT1") (class "Default")
      (node (ref "J3") (pin "1") (pinfunction "1_1") (pintype "passive"))
      (node (ref "U$1") (pin "23/A9") (pinfunction "23/A9_23/A9") (pintype "bidirectional"))
    )
    (net (code "77") (name "XSHUT2") (class "Default")
      (node (ref "J5") (pin "1") (pinfunction "1_1") (pintype "passive"))
      (node (ref "U$1") (pin "22/A8") (pinfunction "22/A8_22/A8") (pintype "bidirectional"))
    )
    (net (code "78") (name "XSHUT3") (class "Default")
      (node (ref "J7") (pin "1") (pinfunction "1_1") (pintype "passive"))
      (node (ref "U$1") (pin "48") (pinfunction "48_48") (pintype "bidirectional"))
    )
    (net (code "79") (name "XSHUT4") (class "Default")
      (node (ref "J9") (pin "1") (pinfunction "1_1") (pintype "passive"))
      (node (ref "U$1") (pin "47") (pinfunction "47_47") (pintype "bidirectional"))
    )
    (net (code "80") (name "unconnected-(J10-Pad2)") (class "Default")
      (node (ref "J10") (pin "2") (pinfunction "2_2") (pintype "passive"))
    )
    (net (code "81") (name "unconnected-(J13-Pad1)") (class "Default")
      (node (ref "J13") (pin "1") (pinfunction "1_1") (pintype "passive"))
    )
    (net (code "82") (name "unconnected-(J13-Pad2)") (class "Default")
      (node (ref "J13") (pin "2") (pinfunction "2_2") (pintype "passive"))
    )
    (net (code "83") (name "unconnected-(J13-Pad3)") (class "Default")
      (node (ref "J13") (pin "3") (pinfunction "3_3") (pintype "passive"))
    )
    (net (code "84") (name "unconnected-(J14-Pad2)") (class "Default")
      (node (ref "J14") (pin "2") (pinfunction "2_2") (pintype "passive"))
    )
    (net (code "85") (name "unconnected-(J14-Pad3)") (class "Default")
      (node (ref "J14") (pin "3") (pinfunction "3_3") (pintype "passive"))
    )
    (net (code "86") (name "unconnected-(J15-Pad2)") (class "Default")
      (node (ref "J15") (pin "2") (pinfunction "2_2") (pintype "passive"))
    )
    (net (code "87") (name "unconnected-(J15-Pad3)") (class "Default")
      (node (ref "J15") (pin "3") (pinfunction "3_3") (pintype "passive"))
    )
    (net (code "88") (name "unconnected-(J17-Pad1)") (class "Default")
      (node (ref "J17") (pin "1") (pinfunction "1_1") (pintype "passive"))
    )
    (net (code "89") (name "unconnected-(J19-Pad2)") (class "Default")
      (node (ref "J19") (pin "2") (pinfunction "2_2") (pintype "passive"))
    )
    (net (code "90") (name "unconnected-(J20-Pad1)") (class "Default")
      (node (ref "J20") (pin "1") (pinfunction "1_1") (pintype "passive"))
    )
    (net (code "91") (name "unconnected-(J20-Pad2)") (class "Default")
      (node (ref "J20") (pin "2") (pinfunction "2_2") (pintype "passive"))
    )
    (net (code "92") (name "unconnected-(J20-Pad3)") (class "Default")
      (node (ref "J20") (pin "3") (pinfunction "3_3") (pintype "passive"))
    )
    (net (code "93") (name "unconnected-(J20-Pad4)") (class "Default")
      (node (ref "J20") (pin "4") (pinfunction "4_4") (pintype "passive"))
    )
    (net (code "94") (name "unconnected-(J20-Pad5)") (class "Default")
      (node (ref "J20") (pin "5") (pinfunction "5_5") (pintype "passive"))
    )
    (net (code "95") (name "unconnected-(J20-Pad6)") (class "Default")
      (node (ref "J20") (pin "6") (pinfunction "6_6") (pintype "passive"))
    )
    (net (code "96") (name "unconnected-(J20-Pad7)") (class "Default")
      (node (ref "J20") (pin "7") (pinfunction "7_7") (pintype "passive"))
    )
    (net (code "97") (name "unconnected-(J20-Pad8)") (class "Default")
      (node (ref "J20") (pin "8") (pinfunction "8_8") (pintype "passive"))
    )
    (net (code "98") (name "unconnected-(J20-Pad9)") (class "Default")
      (node (ref "J20") (pin "9") (pinfunction "9_9") (pintype "passive"))
    )
    (net (code "99") (name "unconnected-(J20-Pad10)") (class "Default")
      (node (ref "J20") (pin "10") (pinfunction "10_10") (pintype "passive"))
    )
    (net (code "100") (name "unconnected-(J20-Pad11)") (class "Default")
      (node (ref "J20") (pin "11") (pinfunction "11_11") (pintype "passive"))
    )
    (net (code "101") (name "unconnected-(J20-Pad12)") (class "Default")
      (node (ref "J20") (pin "12") (pinfunction "12_12") (pintype "passive"))
    )
    (net (code "102") (name "unconnected-(J20-Pad13)") (class "Default")
      (node (ref "J20") (pin "13") (pinfunction "13_13") (pintype "passive"))
    )
    (net (code "103") (name "unconnected-(J20-Pad14)") (class "Default")
      (node (ref "J20") (pin "14") (pinfunction "14_14") (pintype "passive"))
    )
    (net (code "104") (name "unconnected-(J20-Pad15)") (class "Default")
      (node (ref "J20") (pin "15") (pinfunction "15_15") (pintype "passive"))
    )
    (net (code "105") (name "unconnected-(J20-Pad16)") (class "Default")
      (node (ref "J20") (pin "16") (pinfunction "16_16") (pintype "passive"))
    )
    (net (code "106") (name "unconnected-(J20-Pad17)") (class "Default")
      (node (ref "J20") (pin "17") (pinfunction "17_17") (pintype "passive"))
    )
    (net (code "107") (name "unconnected-(J20-Pad18)") (class "Default")
      (node (ref "J20") (pin "18") (pinfunction "18_18") (pintype "passive"))
    )
    (net (code "108") (name "unconnected-(J20-Pad19)") (class "Default")
      (node (ref "J20") (pin "19") (pinfunction "19_19") (pintype "passive"))
    )
    (net (code "109") (name "unconnected-(J20-Pad20)") (class "Default")
      (node (ref "J20") (pin "20") (pinfunction "20_20") (pintype "passive"))
    )
    (net (code "110") (name "unconnected-(J20-Pad21)") (class "Default")
      (node (ref "J20") (pin "21") (pinfunction "21_21") (pintype "passive"))
    )
    (net (code "111") (name "unconnected-(J20-Pad22)") (class "Default")
      (node (ref "J20") (pin "22") (pinfunction "22_22") (pintype "passive"))
    )
    (net (code "112") (name "unconnected-(J20-Pad23)") (class "Default")
      (node (ref "J20") (pin "23") (pinfunction "23_23") (pintype "passive"))
    )
    (net (code "113") (name "unconnected-(J20-Pad24)") (class "Default")
      (node (ref "J20") (pin "24") (pinfunction "24_24") (pintype "passive"))
    )
    (net (code "114") (name "unconnected-(J20-Pad25)") (class "Default")
      (node (ref "J20") (pin "25") (pinfunction "25_25") (pintype "passive"))
    )
    (net (code "115") (name "unconnected-(J20-Pad26)") (class "Default")
      (node (ref "J20") (pin "26") (pinfunction "26_26") (pintype "passive"))
    )
    (net (code "116") (name "unconnected-(J20-Pad27)") (class "Default")
      (node (ref "J20") (pin "27") (pinfunction "27_27") (pintype "passive"))
    )
    (net (code "117") (name "unconnected-(J20-Pad28)") (class "Default")
      (node (ref "J20") (pin "28") (pinfunction "28_28") (pintype "passive"))
    )
    (net (code "118") (name "unconnected-(J20-Pad29)") (class "Default")
      (node (ref "J20") (pin "29") (pinfunction "29_29") (pintype "passive"))
    )
    (net (code "119") (name "unconnected-(J20-Pad30)") (class "Default")
      (node (ref "J20") (pin "30") (pinfunction "30_30") (pintype "passive"))
    )
    (net (code "120") (name "unconnected-(J21-Pad1)") (class "Default")
      (node (ref "J21") (pin "1") (pinfunction "1_1") (pintype "passive"))
    )
    (net (code "121") (name "unconnected-(J21-Pad2)") (class "Default")
      (node (ref "J21") (pin "2") (pinfunction "2_2") (pintype "passive"))
    )
    (net (code "122") (name "unconnected-(J21-Pad3)") (class "Default")
      (node (ref "J21") (pin "3") (pinfunction "3_3") (pintype "passive"))
    )
    (net (code "123") (name "unconnected-(J21-Pad4)") (class "Default")
      (node (ref "J21") (pin "4") (pinfunction "4_4") (pintype "passive"))
    )
    (net (code "124") (name "unconnected-(J21-Pad5)") (class "Default")
      (node (ref "J21") (pin "5") (pinfunction "5_5") (pintype "passive"))
    )
    (net (code "125") (name "unconnected-(J21-Pad6)") (class "Default")
      (node (ref "J21") (pin "6") (pinfunction "6_6") (pintype "passive"))
    )
    (net (code "126") (name "unconnected-(J21-Pad7)") (class "Default")
      (node (ref "J21") (pin "7") (pinfunction "7_7") (pintype "passive"))
    )
    (net (code "127") (name "unconnected-(J21-Pad8)") (class "Default")
      (node (ref "J21") (pin "8") (pinfunction "8_8") (pintype "passive"))
    )
    (net (code "128") (name "unconnected-(J21-Pad9)") (class "Default")
      (node (ref "J21") (pin "9") (pinfunction "9_9") (pintype "passive"))
    )
    (net (code "129") (name "unconnected-(J21-Pad10)") (class "Default")
      (node (ref "J21") (pin "10") (pinfunction "10_10") (pintype "passive"))
    )
    (net (code "130") (name "unconnected-(J21-Pad11)") (class "Default")
      (node (ref "J21") (pin "11") (pinfunction "11_11") (pintype "passive"))
    )
    (net (code "131") (name "unconnected-(J21-Pad12)") (class "Default")
      (node (ref "J21") (pin "12") (pinfunction "12_12") (pintype "passive"))
    )
    (net (code "132") (name "unconnected-(J21-Pad13)") (class "Default")
      (node (ref "J21") (pin "13") (pinfunction "13_13") (pintype "passive"))
    )
    (net (code "133") (name "unconnected-(J21-Pad14)") (class "Default")
      (node (ref "J21") (pin "14") (pinfunction "14_14") (pintype "passive"))
    )
    (net (code "134") (name "unconnected-(J21-Pad15)") (class "Default")
      (node (ref "J21") (pin "15") (pinfunction "15_15") (pintype "passive"))
    )
    (net (code "135") (name "unconnected-(J21-Pad16)") (class "Default")
      (node (ref "J21") (pin "16") (pinfunction "16_16") (pintype "passive"))
    )
    (net (code "136") (name "unconnected-(J21-Pad17)") (class "Default")
      (node (ref "J21") (pin "17") (pinfunction "17_17") (pintype "passive"))
    )
    (net (code "137") (name "unconnected-(J21-Pad18)") (class "Default")
      (node (ref "J21") (pin "18") (pinfunction "18_18") (pintype "passive"))
    )
    (net (code "138") (name "unconnected-(J21-Pad19)") (class "Default")
      (node (ref "J21") (pin "19") (pinfunction "19_19") (pintype "passive"))
    )
    (net (code "139") (name "unconnected-(J21-Pad20)") (class "Default")
      (node (ref "J21") (pin "20") (pinfunction "20_20") (pintype "passive"))
    )
    (net (code "140") (name "unconnected-(J21-Pad21)") (class "Default")
      (node (ref "J21") (pin "21") (pinfunction "21_21") (pintype "passive"))
    )
    (net (code "141") (name "unconnected-(J21-Pad22)") (class "Default")
      (node (ref "J21") (pin "22") (pinfunction "22_22") (pintype "passive"))
    )
    (net (code "142") (name "unconnected-(J21-Pad23)") (class "Default")
      (node (ref "J21") (pin "23") (pinfunction "23_23") (pintype "passive"))
    )
    (net (code "143") (name "unconnected-(J21-Pad24)") (class "Default")
      (node (ref "J21") (pin "24") (pinfunction "24_24") (pintype "passive"))
    )
    (net (code "144") (name "unconnected-(J21-Pad25)") (class "Default")
      (node (ref "J21") (pin "25") (pinfunction "25_25") (pintype "passive"))
    )
    (net (code "145") (name "unconnected-(J21-Pad26)") (class "Default")
      (node (ref "J21") (pin "26") (pinfunction "26_26") (pintype "passive"))
    )
    (net (code "146") (name "unconnected-(J21-Pad27)") (class "Default")
      (node (ref "J21") (pin "27") (pinfunction "27_27") (pintype "passive"))
    )
    (net (code "147") (name "unconnected-(J21-Pad28)") (class "Default")
      (node (ref "J21") (pin "28") (pinfunction "28_28") (pintype "passive"))
    )
    (net (code "148") (name "unconnected-(J21-Pad29)") (class "Default")
      (node (ref "J21") (pin "29") (pinfunction "29_29") (pintype "passive"))
    )
    (net (code "149") (name "unconnected-(J21-Pad30)") (class "Default")
      (node (ref "J21") (pin "30") (pinfunction "30_30") (pintype "passive"))
    )
    (net (code "150") (name "unconnected-(J22-Pad1)") (class "Default")
      (node (ref "J22") (pin "1") (pinfunction "1_1") (pintype "passive"))
    )
    (net (code "151") (name "unconnected-(J22-Pad2)") (class "Default")
      (node (ref "J22") (pin "2") (pinfunction "2_2") (pintype "passive"))
    )
    (net (code "152") (name "unconnected-(J22-Pad3)") (class "Default")
      (node (ref "J22") (pin "3") (pinfunction "3_3") (pintype "passive"))
    )
    (net (code "153") (name "unconnected-(J22-Pad4)") (class "Default")
      (node (ref "J22") (pin "4") (pinfunction "4_4") (pintype "passive"))
    )
    (net (code "154") (name "unconnected-(J22-Pad5)") (class "Default")
      (node (ref "J22") (pin "5") (pinfunction "5_5") (pintype "passive"))
    )
    (net (code "155") (name "unconnected-(J22-Pad6)") (class "Default")
      (node (ref "J22") (pin "6") (pinfunction "6_6") (pintype "passive"))
    )
    (net (code "156") (name "unconnected-(J22-Pad7)") (class "Default")
      (node (ref "J22") (pin "7") (pinfunction "7_7") (pintype "passive"))
    )
    (net (code "157") (name "unconnected-(J22-Pad8)") (class "Default")
      (node (ref "J22") (pin "8") (pinfunction "8_8") (pintype "passive"))
    )
    (net (code "158") (name "unconnected-(J22-Pad9)") (class "Default")
      (node (ref "J22") (pin "9") (pinfunction "9_9") (pintype "passive"))
    )
    (net (code "159") (name "unconnected-(J22-Pad10)") (class "Default")
      (node (ref "J22") (pin "10") (pinfunction "10_10") (pintype "passive"))
    )
    (net (code "160") (name "unconnected-(J22-Pad11)") (class "Default")
      (node (ref "J22") (pin "11") (pinfunction "11_11") (pintype "passive"))
    )
    (net (code "161") (name "unconnected-(J22-Pad12)") (class "Default")
      (node (ref "J22") (pin "12") (pinfunction "12_12") (pintype "passive"))
    )
    (net (code "162") (name "unconnected-(J22-Pad13)") (class "Default")
      (node (ref "J22") (pin "13") (pinfunction "13_13") (pintype "passive"))
    )
    (net (code "163") (name "unconnected-(J22-Pad14)") (class "Default")
      (node (ref "J22") (pin "14") (pinfunction "14_14") (pintype "passive"))
    )
    (net (code "164") (name "unconnected-(J22-Pad15)") (class "Default")
      (node (ref "J22") (pin "15") (pinfunction "15_15") (pintype "passive"))
    )
    (net (code "165") (name "unconnected-(J22-Pad16)") (class "Default")
      (node (ref "J22") (pin "16") (pinfunction "16_16") (pintype "passive"))
    )
    (net (code "166") (name "unconnected-(J22-Pad17)") (class "Default")
      (node (ref "J22") (pin "17") (pinfunction "17_17") (pintype "passive"))
    )
    (net (code "167") (name "unconnected-(J22-Pad18)") (class "Default")
      (node (ref "J22") (pin "18") (pinfunction "18_18") (pintype "passive"))
    )
    (net (code "168") (name "unconnected-(J22-Pad19)") (class "Default")
      (node (ref "J22") (pin "19") (pinfunction "19_19") (pintype "passive"))
    )
    (net (code "169") (name "unconnected-(J22-Pad20)") (class "Default")
      (node (ref "J22") (pin "20") (pinfunction "20_20") (pintype "passive"))
    )
    (net (code "170") (name "unconnected-(J23-Pad1)") (class "Default")
      (node (ref "J23") (pin "1") (pinfunction "1_1") (pintype "passive"))
    )
    (net (code "171") (name "unconnected-(J23-Pad2)") (class "Default")
      (node (ref "J23") (pin "2") (pinfunction "2_2") (pintype "passive"))
    )
    (net (code "172") (name "unconnected-(J23-Pad3)") (class "Default")
      (node (ref "J23") (pin "3") (pinfunction "3_3") (pintype "passive"))
    )
    (net (code "173") (name "unconnected-(J23-Pad4)") (class "Default")
      (node (ref "J23") (pin "4") (pinfunction "4_4") (pintype "passive"))
    )
    (net (code "174") (name "unconnected-(J23-Pad5)") (class "Default")
      (node (ref "J23") (pin "5") (pinfunction "5_5") (pintype "passive"))
    )
    (net (code "175") (name "unconnected-(J23-Pad6)") (class "Default")
      (node (ref "J23") (pin "6") (pinfunction "6_6") (pintype "passive"))
    )
    (net (code "176") (name "unconnected-(J23-Pad7)") (class "Default")
      (node (ref "J23") (pin "7") (pinfunction "7_7") (pintype "passive"))
    )
    (net (code "177") (name "unconnected-(J23-Pad8)") (class "Default")
      (node (ref "J23") (pin "8") (pinfunction "8_8") (pintype "passive"))
    )
    (net (code "178") (name "unconnected-(J23-Pad9)") (class "Default")
      (node (ref "J23") (pin "9") (pinfunction "9_9") (pintype "passive"))
    )
    (net (code "179") (name "unconnected-(J23-Pad10)") (class "Default")
      (node (ref "J23") (pin "10") (pinfunction "10_10") (pintype "passive"))
    )
    (net (code "180") (name "unconnected-(J23-Pad11)") (class "Default")
      (node (ref "J23") (pin "11") (pinfunction "11_11") (pintype "passive"))
    )
    (net (code "181") (name "unconnected-(J23-Pad12)") (class "Default")
      (node (ref "J23") (pin "12") (pinfunction "12_12") (pintype "passive"))
    )
    (net (code "182") (name "unconnected-(J23-Pad13)") (class "Default")
      (node (ref "J23") (pin "13") (pinfunction "13_13") (pintype "passive"))
    )
    (net (code "183") (name "unconnected-(J23-Pad14)") (class "Default")
      (node (ref "J23") (pin "14") (pinfunction "14_14") (pintype "passive"))
    )
    (net (code "184") (name "unconnected-(J23-Pad15)") (class "Default")
      (node (ref "J23") (pin "15") (pinfunction "15_15") (pintype "passive"))
    )
    (net (code "185") (name "unconnected-(J23-Pad16)") (class "Default")
      (node (ref "J23") (pin "16") (pinfunction "16_16") (pintype "passive"))
    )
    (net (code "186") (name "unconnected-(J23-Pad17)") (class "Default")
      (node (ref "J23") (pin "17") (pinfunction "17_17") (pintype "passive"))
    )
    (net (code "187") (name "unconnected-(J23-Pad18)") (class "Default")
      (node (ref "J23") (pin "18") (pinfunction "18_18") (pintype "passive"))
    )
    (net (code "188") (name "unconnected-(J23-Pad19)") (class "Default")
      (node (ref "J23") (pin "19") (pinfunction "19_19") (pintype "passive"))
    )
    (net (code "189") (name "unconnected-(J23-Pad20)") (class "Default")
      (node (ref "J23") (pin "20") (pinfunction "20_20") (pintype "passive"))
    )
    (net (code "190") (name "unconnected-(S1-S-Pad3)") (class "Default")
      (node (ref "S1") (pin "3") (pinfunction "S_3") (pintype "passive"))
    )
    (net (code "191") (name "unconnected-(U$1-Pad3V3)") (class "Default")
      (node (ref "U$1") (pin "3V3") (pinfunction "3V3_3V3") (pintype "bidirectional"))
    )
    (net (code "192") (name "unconnected-(U$1-Pad3V3_LO)") (class "Default")
      (node (ref "U$1") (pin "3V3_LO") (pinfunction "3V3_LO_3V3_LO") (pintype "bidirectional"))
    )
    (net (code "193") (name "unconnected-(U$1-PadAGND)") (class "Default")
      (node (ref "U$1") (pin "AGND") (pinfunction "AGND_AGND") (pintype "bidirectional"))
    )
    (net (code "194") (name "unconnected-(U$1-PadAREF)") (class "Default")
      (node (ref "U$1") (pin "AREF") (pinfunction "AREF_AREF") (pintype "bidirectional"))
    )
    (net (code "195") (name "unconnected-(U$1-PadGND2)") (class "Default")
      (node (ref "U$1") (pin "GND2") (pinfunction "GND2_GND2") (pintype "bidirectional"))
    )
    (net (code "196") (name "unconnected-(U$1-PadVUSB)") (class "Default")
      (node (ref "U$1") (pin "VUSB") (pinfunction "VUSB_VUSB") (pintype "bidirectional"))
    )
    (net (code "197") (name "unconnected-(U$2-0{slash}RX3{slash}I2C2_SDA-Pad22)") (class "Default")
      (node (ref "U$2") (pin "22") (pinfunction "0/RX3/I2C2_SDA_22") (pintype "bidirectional"))
    )
    (net (code "198") (name "unconnected-(U$2-1{slash}TX3{slash}I2C2_SCL-Pad23)") (class "Default")
      (node (ref "U$2") (pin "23") (pinfunction "1/TX3/I2C2_SCL_23") (pintype "bidirectional"))
    )
    (net (code "199") (name "unconnected-(U$2-2{slash}BOOT1-Pad24)") (class "Default")
      (node (ref "U$2") (pin "24") (pinfunction "2/BOOT1_24") (pintype "bidirectional"))
    )
    (net (code "200") (name "unconnected-(U$2-13-Pad36)") (class "Default")
      (node (ref "U$2") (pin "36") (pinfunction "13_36") (pintype "bidirectional"))
    )
    (net (code "201") (name "unconnected-(U$2-14-Pad37)") (class "Default")
      (node (ref "U$2") (pin "37") (pinfunction "14_37") (pintype "bidirectional"))
    )
    (net (code "202") (name "unconnected-(U$2-17-Pad6)") (class "Default")
      (node (ref "U$2") (pin "6") (pinfunction "17_6") (pintype "bidirectional"))
    )
    (net (code "203") (name "unconnected-(U$2-18-Pad7)") (class "Default")
      (node (ref "U$2") (pin "7") (pinfunction "18_7") (pintype "bidirectional"))
    )
    (net (code "204") (name "unconnected-(U$2-19-Pad8)") (class "Default")
      (node (ref "U$2") (pin "8") (pinfunction "19_8") (pintype "bidirectional"))
    )
    (net (code "205") (name "unconnected-(U$2-20-Pad9)") (class "Default")
      (node (ref "U$2") (pin "9") (pinfunction "20_9") (pintype "bidirectional"))
    )
    (net (code "206") (name "unconnected-(U$2-21-Pad10)") (class "Default")
      (node (ref "U$2") (pin "10") (pinfunction "21_10") (pintype "bidirectional"))
    )
    (net (code "207") (name "unconnected-(U$2-22-Pad11)") (class "Default")
      (node (ref "U$2") (pin "11") (pinfunction "22_11") (pintype "bidirectional"))
    )
    (net (code "208") (name "unconnected-(U$2-23{slash}USB_DP-Pad12)") (class "Default")
      (node (ref "U$2") (pin "12") (pinfunction "23/USB_DP_12") (pintype "bidirectional"))
    )
    (net (code "209") (name "unconnected-(U$2-24{slash}USB_DM-Pad13)") (class "Default")
      (node (ref "U$2") (pin "13") (pinfunction "24/USB_DM_13") (pintype "bidirectional"))
    )
    (net (code "210") (name "unconnected-(U$2-25{slash}PWM{slash}RX1-Pad14)") (class "Default")
      (node (ref "U$2") (pin "14") (pinfunction "25/PWM/RX1_14") (pintype "bidirectional"))
    )
    (net (code "211") (name "unconnected-(U$2-28{slash}SPI2_MOSI-Pad17)") (class "Default")
      (node (ref "U$2") (pin "17") (pinfunction "28/SPI2_MOSI_17") (pintype "bidirectional"))
    )
    (net (code "212") (name "unconnected-(U$2-29{slash}SPI2_MISO-Pad18)") (class "Default")
      (node (ref "U$2") (pin "18") (pinfunction "29/SPI2_MISO_18") (pintype "bidirectional"))
    )
    (net (code "213") (name "unconnected-(U$2-30{slash}SPI2_SCK-Pad19)") (class "Default")
      (node (ref "U$2") (pin "19") (pinfunction "30/SPI2_SCK_19") (pintype "bidirectional"))
    )
    (net (code "214") (name "unconnected-(U$2-31{slash}SPI2_SS-Pad20)") (class "Default")
      (node (ref "U$2") (pin "20") (pinfunction "31/SPI2_SS_20") (pintype "bidirectional"))
    )
    (net (code "215") (name "unconnected-(U$2-AV+-Pad40)") (class "Default")
      (node (ref "U$2") (pin "40") (pinfunction "AV+_40") (pintype "bidirectional"))
    )
    (net (code "216") (name "unconnected-(U$2-AV--Pad39)") (class "Default")
      (node (ref "U$2") (pin "39") (pinfunction "AV-_39") (pintype "bidirectional"))
    )
    (net (code "217") (name "unconnected-(U$2-BUT-Pad3)") (class "Default")
      (node (ref "U$2") (pin "3") (pinfunction "BUT_3") (pintype "bidirectional"))
    )
    (net (code "218") (name "unconnected-(U$2-RESET-Pad34)") (class "Default")
      (node (ref "U$2") (pin "34") (pinfunction "RESET_34") (pintype "bidirectional"))
    )
    (net (code "219") (name "unconnected-(U$2-VBAT-Pad38)") (class "Default")
      (node (ref "U$2") (pin "38") (pinfunction "VBAT_38") (pintype "bidirectional"))
    )
    (net (code "220") (name "unconnected-(U$2-VCC-Pad1)") (class "Default")
      (node (ref "U$2") (pin "1") (pinfunction "VCC_1") (pintype "bidirectional"))
    )
    (net (code "221") (name "unconnected-(U$3D-I0-PadP12)") (class "Default")
      (node (ref "U$3") (pin "P12") (pinfunction "I0_P12") (pintype "input"))
    )
    (net (code "222") (name "unconnected-(U$3D-I1-PadP13)") (class "Default")
      (node (ref "U$3") (pin "P13") (pinfunction "I1_P13") (pintype "input"))
    )
    (net (code "223") (name "unconnected-(U$3D-O-PadP11)") (class "Default")
      (node (ref "U$3") (pin "P11") (pinfunction "O_P11") (pintype "output"))
    )
    (net (code "224") (name "unconnected-(U3-NC-Pad3)") (class "Default")
      (node (ref "U3") (pin "3") (pinfunction "NC_3") (pintype "bidirectional"))
    )
    (net (code "225") (name "unconnected-(U3-NC-Pad10)") (class "Default")
      (node (ref "U3") (pin "10") (pinfunction "NC_10") (pintype "bidirectional"))
    )
    (net (code "226") (name "unconnected-(U3-NC-Pad11)") (class "Default")
      (node (ref "U3") (pin "11") (pinfunction "NC_11") (pintype "bidirectional"))
    )
  )
)
